# HDMI.net
KiCad netlist of a schematic drawn in Altium Designer
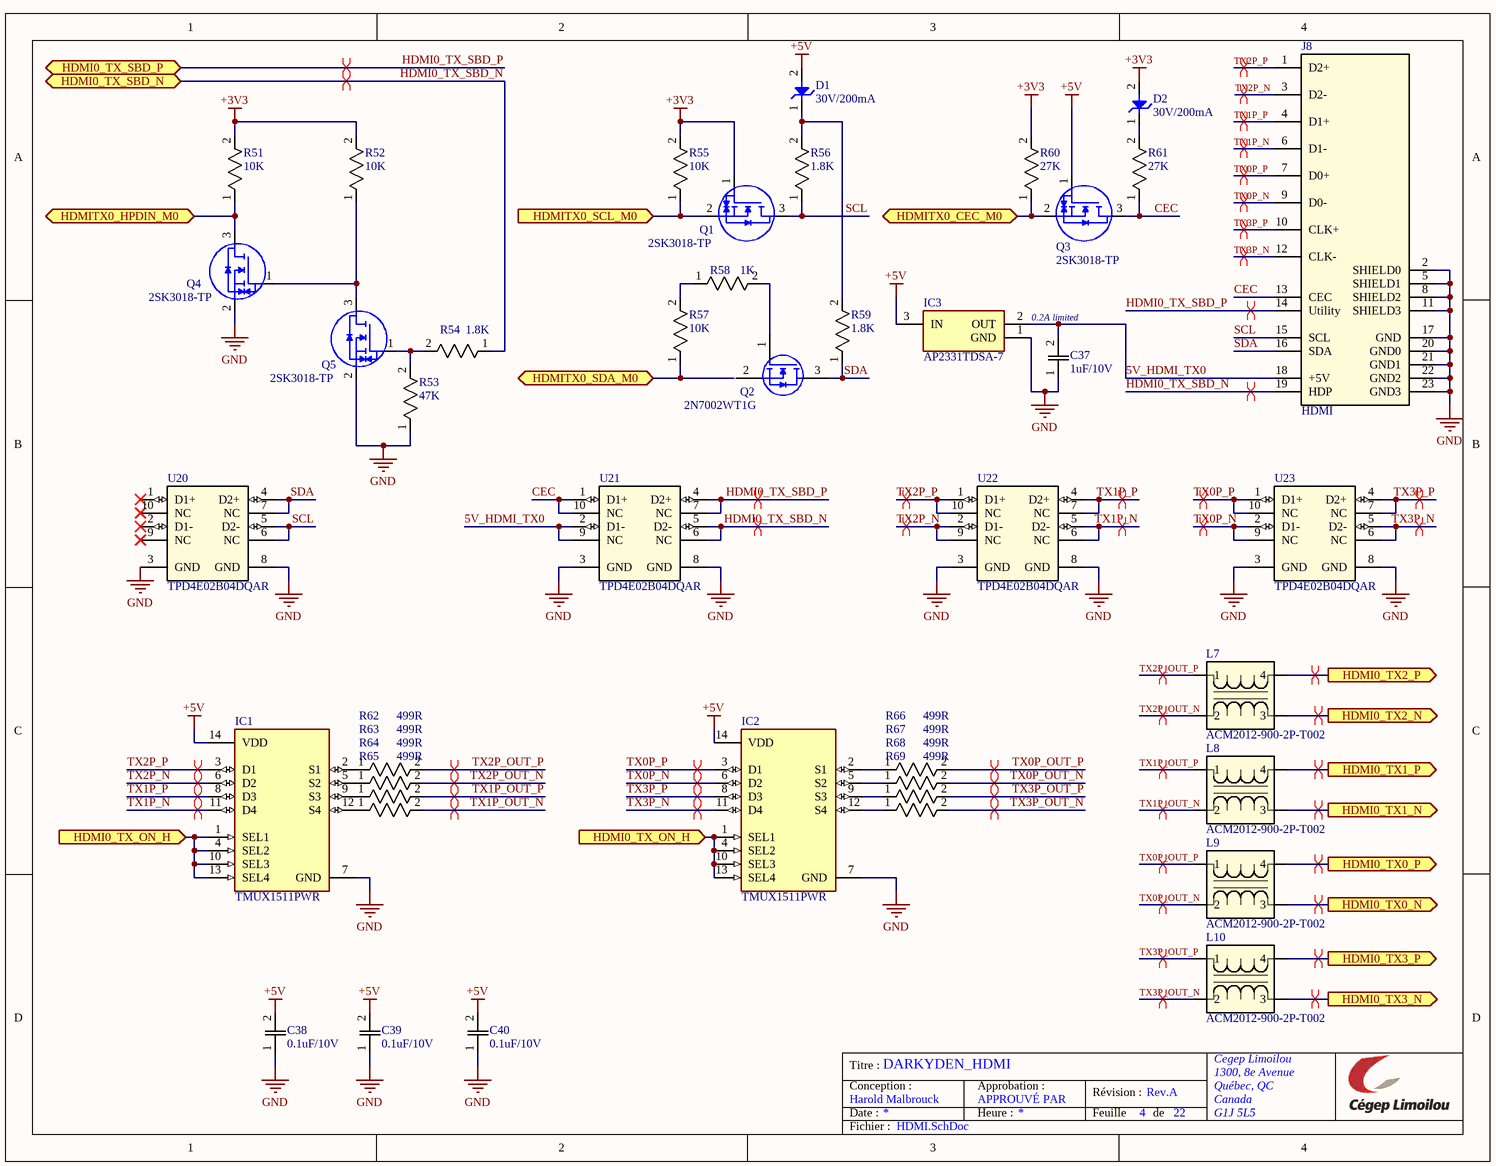
[diagram p0: HDMI.SchDoc]

(export (version "E")
  (design (tool "Eeschema 10.0.6"))
  (components
    (comp (ref "C37")
      (value "1uF/10V")
      (footprint "CAPC220145_88N_KEM")
      (description "Multilayer Ceramic Capacitors MLCC - SMD/SMT 10V 1uF X7R 0805 10%")
      (fields
        (field (name "MANUFACTURER") "KEMET")
        (field (name "MANUFACTURER PART NUMBER") "C0805C105K8RACTU")
      )
      (libsource (lib "C0805C105K8RACTU") (part "C0805C105K8RACTU"))
    )
    (comp (ref "C38")
      (value "0.1uF/10V")
      (footprint "CAPC220145_88N_KEM")
      (description "Cap Ceramic 0.1uF 10V X7R 5% Pad SMD 0805 125C T/R")
      (fields
        (field (name "MANUFACTURER") "KEMET")
        (field (name "MANUFACTURER PART NUMBER") "C0805C104J8RACTU")
      )
      (libsource (lib "C0805C104J8RACTU") (part "C0805C104J8RACTU"))
    )
    (comp (ref "C39")
      (value "0.1uF/10V")
      (footprint "CAPC220145_88N_KEM")
      (description "Cap Ceramic 0.1uF 10V X7R 5% Pad SMD 0805 125C T/R")
      (fields
        (field (name "MANUFACTURER") "KEMET")
        (field (name "MANUFACTURER PART NUMBER") "C0805C104J8RACTU")
      )
      (libsource (lib "C0805C104J8RACTU") (part "C0805C104J8RACTU"))
    )
    (comp (ref "C40")
      (value "0.1uF/10V")
      (footprint "CAPC220145_88N_KEM")
      (description "Cap Ceramic 0.1uF 10V X7R 5% Pad SMD 0805 125C T/R")
      (fields
        (field (name "MANUFACTURER") "KEMET")
        (field (name "MANUFACTURER PART NUMBER") "C0805C104J8RACTU")
      )
      (libsource (lib "C0805C104J8RACTU") (part "C0805C104J8RACTU"))
    )
    (comp (ref "D1")
      (value "30V/200mA")
      (footprint "SamacSys:SODFL1608X70N")
      (description "SCHOTTKY BARRIER DIODE Rectifier Diode, Schottky, 1 Phase, 1 Element, 0.2A, 30V V(RRM), Silicon")
      (fields
        (field (name "MANUFACTURER_PART_NUMBER") "RB521S30T1G")
        (field (name "MOUSER PART NUMBER") "863-RB521S30T1G")
      )
      (libsource (lib "SamacSys") (part "RB521S30T1G"))
    )
    (comp (ref "D2")
      (value "30V/200mA")
      (footprint "SamacSys:SODFL1608X70N")
      (description "SCHOTTKY BARRIER DIODE Rectifier Diode, Schottky, 1 Phase, 1 Element, 0.2A, 30V V(RRM), Silicon")
      (fields
        (field (name "MANUFACTURER_PART_NUMBER") "RB521S30T1G")
        (field (name "MOUSER PART NUMBER") "863-RB521S30T1G")
      )
      (libsource (lib "SamacSys") (part "RB521S30T1G"))
    )
    (comp (ref "IC1")
      (value "TMUX1511PWR")
      (footprint "SamacSys:SOP65P640X120-14N")
      (fields
        (field (name "MOUSER PART NUMBER") "595-TMUX1511PWR")
        (field (name "MANUFACTURER") "Texas Instruments")
      )
      (libsource (lib "SamacSys") (part "TMUX1511PWR"))
    )
    (comp (ref "IC2")
      (value "TMUX1511PWR")
      (footprint "SamacSys:SOP65P640X120-14N")
      (fields
        (field (name "MOUSER PART NUMBER") "595-TMUX1511PWR")
        (field (name "MANUFACTURER") "Texas Instruments")
      )
      (libsource (lib "SamacSys") (part "TMUX1511PWR"))
    )
    (comp (ref "IC3")
      (value "AP2331TDSA-7")
      (footprint "SamacSys:SOT96P240X110-3N")
      (description "USB Power Switch Single 5.2V 0.4A 3-Pin SOT-23 T/R")
      (fields (field (name "MOUSER PART NUMBER") "621-AP2331TDSA-7") (field (name "MANUFACTURER") "Diodes"))
      (libsource (lib "SamacSys") (part "AP2331TDSA-7"))
    )
    (comp (ref "J8")
      (value "HDMI")
      (footprint "CONN19_2001-1-2-21-00-BK_CNC")
      (description "2001-1-2-21-00-BK")
      (libsource (lib "HDMI") (part "HDMI"))
    )
    (comp (ref "L7")
      (value "ACM2012-900-2P-T002")
      (footprint "SamacSys:ACM20129002PT002")
      (description "Ferrite Beads Wirewound Common Mode Filter 90Ohm 100MHz 400mA 0805 T/R")
      (fields (field (name "MOUSER PART NUMBER") "810-ACM20129002PT002") (field (name "MANUFACTURER") "TDK"))
      (libsource (lib "SamacSys") (part "ACM2012-900-2P-T002"))
    )
    (comp (ref "L8")
      (value "ACM2012-900-2P-T002")
      (footprint "SamacSys:ACM20129002PT002")
      (description "Ferrite Beads Wirewound Common Mode Filter 90Ohm 100MHz 400mA 0805 T/R")
      (fields (field (name "MOUSER PART NUMBER") "810-ACM20129002PT002") (field (name "MANUFACTURER") "TDK"))
      (libsource (lib "SamacSys") (part "ACM2012-900-2P-T002"))
    )
    (comp (ref "L9")
      (value "ACM2012-900-2P-T002")
      (footprint "SamacSys:ACM20129002PT002")
      (description "Ferrite Beads Wirewound Common Mode Filter 90Ohm 100MHz 400mA 0805 T/R")
      (fields (field (name "MOUSER PART NUMBER") "810-ACM20129002PT002") (field (name "MANUFACTURER") "TDK"))
      (libsource (lib "SamacSys") (part "ACM2012-900-2P-T002"))
    )
    (comp (ref "L10")
      (value "ACM2012-900-2P-T002")
      (footprint "SamacSys:ACM20129002PT002")
      (description "Ferrite Beads Wirewound Common Mode Filter 90Ohm 100MHz 400mA 0805 T/R")
      (fields (field (name "MOUSER PART NUMBER") "810-ACM20129002PT002") (field (name "MANUFACTURER") "TDK"))
      (libsource (lib "SamacSys") (part "ACM2012-900-2P-T002"))
    )
    (comp (ref "Q1")
      (value "2SK3018-TP")
      (footprint "SamacSys:SOT65P228X120-3N")
      (description "N-Channel 30 V 100mA (Ta) 200mW (Ta) Surface Mount SOT-323")
      (fields (field (name "MOUSER PART NUMBER") "833-2SK3018-TP"))
      (libsource (lib "SamacSys") (part "2SK3018-TP"))
    )
    (comp (ref "Q2")
      (value "2N7002WT1G")
      (footprint "SOT-323-3_2P2X1P35_ONS")
      (description "No Description Available")
      (libsource (lib "2N7002WT1G") (part "2N7002WT1G"))
    )
    (comp (ref "Q3")
      (value "2SK3018-TP")
      (footprint "SamacSys:SOT65P228X120-3N")
      (description "N-Channel 30 V 100mA (Ta) 200mW (Ta) Surface Mount SOT-323")
      (fields (field (name "MOUSER PART NUMBER") "833-2SK3018-TP"))
      (libsource (lib "SamacSys") (part "2SK3018-TP"))
    )
    (comp (ref "Q4")
      (value "2SK3018-TP")
      (footprint "SamacSys:SOT65P228X120-3N")
      (description "N-Channel 30 V 100mA (Ta) 200mW (Ta) Surface Mount SOT-323")
      (fields (field (name "MOUSER PART NUMBER") "833-2SK3018-TP"))
      (libsource (lib "SamacSys") (part "2SK3018-TP"))
    )
    (comp (ref "Q5")
      (value "2SK3018-TP")
      (footprint "SamacSys:SOT65P228X120-3N")
      (description "N-Channel 30 V 100mA (Ta) 200mW (Ta) Surface Mount SOT-323")
      (fields (field (name "MOUSER PART NUMBER") "833-2SK3018-TP"))
      (libsource (lib "SamacSys") (part "2SK3018-TP"))
    )
    (comp (ref "R51")
      (value "10K")
      (footprint "SamacSys:ERJ3EKF1000V")
      (description "10K Ohm 5% Res Thick Film 0603  0.1W(1/10W) ±200ppm/C Pad SMD Automotive T/R")
      (fields
        (field (name "MANUFACTURER_PART_NUMBER") "ERJ-3GEYJ103V")
        (field (name "MOUSER PART NUMBER") "667-ERJ-3GEYJ103V")
      )
      (libsource (lib "SamacSys") (part "ERJ-3GEYJ103V"))
    )
    (comp (ref "R52")
      (value "10K")
      (footprint "SamacSys:ERJ3EKF1000V")
      (description "10K Ohm 5% Res Thick Film 0603  0.1W(1/10W) ±200ppm/C Pad SMD Automotive T/R")
      (fields
        (field (name "MANUFACTURER_PART_NUMBER") "ERJ-3GEYJ103V")
        (field (name "MOUSER PART NUMBER") "667-ERJ-3GEYJ103V")
      )
      (libsource (lib "SamacSys") (part "ERJ-3GEYJ103V"))
    )
    (comp (ref "R53")
      (value "47K")
      (footprint "RC0603N_PAN")
      (description "Resistor Thick Film 0603 47K Ohm 5% 1/10W 200ppm/C Molded SMD Punched Carrier T/R")
      (fields
        (field (name "MANUFACTURER") "Panasonic")
        (field (name "MANUFACTURER PART NUMBER") "ERJ-3GEYJ473V")
      )
      (libsource (lib "ERJ-3GEYJ473V") (part "ERJ-3GEYJ473V"))
    )
    (comp (ref "R54")
      (value "1.8K")
      (footprint "RC0603N_PAN")
      (description "SMD Chip Resistor, 1.8 kOhm, ± 5%, 100 mW, 0603 [1608 Metric], Thick Film, General Purpose")
      (fields
        (field (name "MANUFACTURER") "Panasonic")
        (field (name "MANUFACTURER PART NUMBER") "ERJ-3GEYJ182V")
      )
      (libsource (lib "ERJ-3GEYJ182V") (part "ERJ-3GEYJ182V"))
    )
    (comp (ref "R55")
      (value "10K")
      (footprint "SamacSys:ERJ3EKF1000V")
      (description "10K Ohm 5% Res Thick Film 0603  0.1W(1/10W) ±200ppm/C Pad SMD Automotive T/R")
      (fields
        (field (name "MANUFACTURER_PART_NUMBER") "ERJ-3GEYJ103V")
        (field (name "MOUSER PART NUMBER") "667-ERJ-3GEYJ103V")
      )
      (libsource (lib "SamacSys") (part "ERJ-3GEYJ103V"))
    )
    (comp (ref "R56")
      (value "1.8K")
      (footprint "RC0603N_PAN")
      (description "SMD Chip Resistor, 1.8 kOhm, ± 5%, 100 mW, 0603 [1608 Metric], Thick Film, General Purpose")
      (fields
        (field (name "MANUFACTURER") "Panasonic")
        (field (name "MANUFACTURER PART NUMBER") "ERJ-3GEYJ182V")
      )
      (libsource (lib "ERJ-3GEYJ182V") (part "ERJ-3GEYJ182V"))
    )
    (comp (ref "R57")
      (value "10K")
      (footprint "SamacSys:ERJ3EKF1000V")
      (description "10K Ohm 5% Res Thick Film 0603  0.1W(1/10W) ±200ppm/C Pad SMD Automotive T/R")
      (fields
        (field (name "MANUFACTURER_PART_NUMBER") "ERJ-3GEYJ103V")
        (field (name "MOUSER PART NUMBER") "667-ERJ-3GEYJ103V")
      )
      (libsource (lib "SamacSys") (part "ERJ-3GEYJ103V"))
    )
    (comp (ref "R58")
      (value "1K")
      (footprint "SamacSys:RESC1608X55N")
      (description "1K Ohm 1% 1/10W Res Thick Film 0603 ±100ppm/°C Molded SMD Punched Carrier T/R")
      (fields
        (field (name "MANUFACTURER_PART_NUMBER") "ERJ-3EKF1001V")
        (field (name "MOUSER PART NUMBER") "667-ERJ-3EKF1001V")
      )
      (libsource (lib "SamacSys") (part "ERJ-3EKF1001V"))
    )
    (comp (ref "R59")
      (value "1.8K")
      (footprint "RC0603N_PAN")
      (description "SMD Chip Resistor, 1.8 kOhm, ± 5%, 100 mW, 0603 [1608 Metric], Thick Film, General Purpose")
      (fields
        (field (name "MANUFACTURER") "Panasonic")
        (field (name "MANUFACTURER PART NUMBER") "ERJ-3GEYJ182V")
      )
      (libsource (lib "ERJ-3GEYJ182V") (part "ERJ-3GEYJ182V"))
    )
    (comp (ref "R60")
      (value "27K")
      (footprint "RC0603N_PAN")
      (description "Res Thick Film 0603 27K Ohm 1% 1/10W ±100ppm/°C Molded SMD Punched Carrier T/R")
      (fields
        (field (name "MANUFACTURER") "Panasonic")
        (field (name "MANUFACTURER PART NUMBER") "ERJ-3EKF2702V")
      )
      (libsource (lib "ERJ-3EKF2702V") (part "ERJ-3EKF2702V"))
    )
    (comp (ref "R61")
      (value "27K")
      (footprint "RC0603N_PAN")
      (description "Res Thick Film 0603 27K Ohm 1% 1/10W ±100ppm/°C Molded SMD Punched Carrier T/R")
      (fields
        (field (name "MANUFACTURER") "Panasonic")
        (field (name "MANUFACTURER PART NUMBER") "ERJ-3EKF2702V")
      )
      (libsource (lib "ERJ-3EKF2702V") (part "ERJ-3EKF2702V"))
    )
    (comp (ref "R62")
      (value "499R")
      (footprint "RC0603N_PAN")
      (description "SMD Chip Resistor, 499 Ohm, ï¿½ 1%, 100 mW, 0603 [1608 Metric], Thick Film, Precision")
      (fields
        (field (name "MANUFACTURER") "Panasonic")
        (field (name "MANUFACTURER PART NUMBER") "ERJ-3EKF4990V")
      )
      (libsource (lib "ERJ-3EKF4990V") (part "ERJ-3EKF4990V"))
    )
    (comp (ref "R63")
      (value "499R")
      (footprint "RC0603N_PAN")
      (description "SMD Chip Resistor, 499 Ohm, ï¿½ 1%, 100 mW, 0603 [1608 Metric], Thick Film, Precision")
      (fields
        (field (name "MANUFACTURER") "Panasonic")
        (field (name "MANUFACTURER PART NUMBER") "ERJ-3EKF4990V")
      )
      (libsource (lib "ERJ-3EKF4990V") (part "ERJ-3EKF4990V"))
    )
    (comp (ref "R64")
      (value "499R")
      (footprint "RC0603N_PAN")
      (description "SMD Chip Resistor, 499 Ohm, ï¿½ 1%, 100 mW, 0603 [1608 Metric], Thick Film, Precision")
      (fields
        (field (name "MANUFACTURER") "Panasonic")
        (field (name "MANUFACTURER PART NUMBER") "ERJ-3EKF4990V")
      )
      (libsource (lib "ERJ-3EKF4990V") (part "ERJ-3EKF4990V"))
    )
    (comp (ref "R65")
      (value "499R")
      (footprint "RC0603N_PAN")
      (description "SMD Chip Resistor, 499 Ohm, ï¿½ 1%, 100 mW, 0603 [1608 Metric], Thick Film, Precision")
      (fields
        (field (name "MANUFACTURER") "Panasonic")
        (field (name "MANUFACTURER PART NUMBER") "ERJ-3EKF4990V")
      )
      (libsource (lib "ERJ-3EKF4990V") (part "ERJ-3EKF4990V"))
    )
    (comp (ref "R66")
      (value "499R")
      (footprint "RC0603N_PAN")
      (description "SMD Chip Resistor, 499 Ohm, ï¿½ 1%, 100 mW, 0603 [1608 Metric], Thick Film, Precision")
      (fields
        (field (name "MANUFACTURER") "Panasonic")
        (field (name "MANUFACTURER PART NUMBER") "ERJ-3EKF4990V")
      )
      (libsource (lib "ERJ-3EKF4990V") (part "ERJ-3EKF4990V"))
    )
    (comp (ref "R67")
      (value "499R")
      (footprint "RC0603N_PAN")
      (description "SMD Chip Resistor, 499 Ohm, ï¿½ 1%, 100 mW, 0603 [1608 Metric], Thick Film, Precision")
      (fields
        (field (name "MANUFACTURER") "Panasonic")
        (field (name "MANUFACTURER PART NUMBER") "ERJ-3EKF4990V")
      )
      (libsource (lib "ERJ-3EKF4990V") (part "ERJ-3EKF4990V"))
    )
    (comp (ref "R68")
      (value "499R")
      (footprint "RC0603N_PAN")
      (description "SMD Chip Resistor, 499 Ohm, ï¿½ 1%, 100 mW, 0603 [1608 Metric], Thick Film, Precision")
      (fields
        (field (name "MANUFACTURER") "Panasonic")
        (field (name "MANUFACTURER PART NUMBER") "ERJ-3EKF4990V")
      )
      (libsource (lib "ERJ-3EKF4990V") (part "ERJ-3EKF4990V"))
    )
    (comp (ref "R69")
      (value "499R")
      (footprint "RC0603N_PAN")
      (description "SMD Chip Resistor, 499 Ohm, ï¿½ 1%, 100 mW, 0603 [1608 Metric], Thick Film, Precision")
      (fields
        (field (name "MANUFACTURER") "Panasonic")
        (field (name "MANUFACTURER PART NUMBER") "ERJ-3EKF4990V")
      )
      (libsource (lib "ERJ-3EKF4990V") (part "ERJ-3EKF4990V"))
    )
    (comp (ref "U20")
      (value "TPD4E02B04DQAR")
      (footprint "DQA0010A")
      (description "TVS DIODE 3.6V 8.8V 10USON / 4-Channel ESD Protection Diode for USB Type-C and HDMI 2.0")
      (fields (field (name "MANUFACTURER") "Texas Instruments"))
      (libsource (lib "TPD4E02B04DQAR") (part "TPD4E02B04DQAR"))
    )
    (comp (ref "U21")
      (value "TPD4E02B04DQAR")
      (footprint "DQA0010A")
      (description "TVS DIODE 3.6V 8.8V 10USON / 4-Channel ESD Protection Diode for USB Type-C and HDMI 2.0")
      (fields (field (name "MANUFACTURER") "Texas Instruments"))
      (libsource (lib "TPD4E02B04DQAR") (part "TPD4E02B04DQAR"))
    )
    (comp (ref "U22")
      (value "TPD4E02B04DQAR")
      (footprint "DQA0010A")
      (description "TVS DIODE 3.6V 8.8V 10USON / 4-Channel ESD Protection Diode for USB Type-C and HDMI 2.0")
      (fields (field (name "MANUFACTURER") "Texas Instruments"))
      (libsource (lib "TPD4E02B04DQAR") (part "TPD4E02B04DQAR"))
    )
    (comp (ref "U23")
      (value "TPD4E02B04DQAR")
      (footprint "DQA0010A")
      (description "TVS DIODE 3.6V 8.8V 10USON / 4-Channel ESD Protection Diode for USB Type-C and HDMI 2.0")
      (fields (field (name "MANUFACTURER") "Texas Instruments"))
      (libsource (lib "TPD4E02B04DQAR") (part "TPD4E02B04DQAR"))
    )
  )
  (nets
    (net (code "1") (name "+3V3") (class "Default")
      (node (ref "D2") (pin "2") (pinfunction "A_2") (pintype "passive"))
      (node (ref "Q1") (pin "1") (pinfunction "G_1") (pintype "passive"))
      (node (ref "R51") (pin "2") (pinfunction "2_2") (pintype "passive"))
      (node (ref "R52") (pin "2") (pinfunction "2_2") (pintype "passive"))
      (node (ref "R55") (pin "2") (pinfunction "2_2") (pintype "passive"))
      (node (ref "R60") (pin "2") (pinfunction "2_2") (pintype "passive"))
    )
    (net (code "2") (name "+5V") (class "Default")
      (node (ref "C38") (pin "2") (pinfunction "2_2") (pintype "passive"))
      (node (ref "C39") (pin "2") (pinfunction "2_2") (pintype "passive"))
      (node (ref "C40") (pin "2") (pinfunction "2_2") (pintype "passive"))
      (node (ref "D1") (pin "2") (pinfunction "A_2") (pintype "passive"))
      (node (ref "IC1") (pin "14") (pinfunction "VDD_14") (pintype "power_in"))
      (node (ref "IC2") (pin "14") (pinfunction "VDD_14") (pintype "power_in"))
      (node (ref "IC3") (pin "3") (pinfunction "IN_3") (pintype "passive"))
      (node (ref "Q3") (pin "1") (pinfunction "G_1") (pintype "passive"))
    )
    (net (code "3") (name "/5V_HDMI_TX0") (class "Default")
      (node (ref "C37") (pin "2") (pinfunction "2_2") (pintype "passive"))
      (node (ref "IC3") (pin "2") (pinfunction "OUT_2") (pintype "passive"))
      (node (ref "J8") (pin "18") (pinfunction "+5V_18") (pintype "passive"))
      (node (ref "U21") (pin "2") (pinfunction "D1-_2") (pintype "bidirectional"))
      (node (ref "U21") (pin "9") (pinfunction "NC_9") (pintype "passive"))
    )
    (net (code "4") (name "/CEC") (class "Default")
      (node (ref "J8") (pin "13") (pinfunction "CEC_13") (pintype "passive"))
      (node (ref "Q3") (pin "3") (pinfunction "D_3") (pintype "passive"))
      (node (ref "R61") (pin "1") (pinfunction "1_1") (pintype "passive"))
      (node (ref "U21") (pin "1") (pinfunction "D1+_1") (pintype "bidirectional"))
      (node (ref "U21") (pin "10") (pinfunction "NC_10") (pintype "passive"))
    )
    (net (code "5") (name "/HDMI0_TX0_N") (class "Default")
      (node (ref "L9") (pin "3") (pinfunction "3_3") (pintype "passive"))
    )
    (net (code "6") (name "/HDMI0_TX0_P") (class "Default")
      (node (ref "L9") (pin "4") (pinfunction "4_4") (pintype "passive"))
    )
    (net (code "7") (name "/HDMI0_TX1_N") (class "Default")
      (node (ref "L8") (pin "3") (pinfunction "3_3") (pintype "passive"))
    )
    (net (code "8") (name "/HDMI0_TX1_P") (class "Default")
      (node (ref "L8") (pin "4") (pinfunction "4_4") (pintype "passive"))
    )
    (net (code "9") (name "/HDMI0_TX2_N") (class "Default")
      (node (ref "L7") (pin "3") (pinfunction "3_3") (pintype "passive"))
    )
    (net (code "10") (name "/HDMI0_TX2_P") (class "Default")
      (node (ref "L7") (pin "4") (pinfunction "4_4") (pintype "passive"))
    )
    (net (code "11") (name "/HDMI0_TX3_N") (class "Default")
      (node (ref "L10") (pin "3") (pinfunction "3_3") (pintype "passive"))
    )
    (net (code "12") (name "/HDMI0_TX3_P") (class "Default")
      (node (ref "L10") (pin "4") (pinfunction "4_4") (pintype "passive"))
    )
    (net (code "13") (name "/HDMI0_TX_ON_H") (class "Default")
      (node (ref "IC1") (pin "1") (pinfunction "SEL1_1") (pintype "input"))
      (node (ref "IC1") (pin "10") (pinfunction "SEL3_10") (pintype "input"))
      (node (ref "IC1") (pin "13") (pinfunction "SEL4_13") (pintype "input"))
      (node (ref "IC1") (pin "4") (pinfunction "SEL2_4") (pintype "input"))
      (node (ref "IC2") (pin "1") (pinfunction "SEL1_1") (pintype "input"))
      (node (ref "IC2") (pin "10") (pinfunction "SEL3_10") (pintype "input"))
      (node (ref "IC2") (pin "13") (pinfunction "SEL4_13") (pintype "input"))
      (node (ref "IC2") (pin "4") (pinfunction "SEL2_4") (pintype "input"))
    )
    (net (code "14") (name "/HDMI0_TX_SBD_N") (class "Default")
      (node (ref "J8") (pin "19") (pinfunction "HDP_19") (pintype "passive"))
      (node (ref "R54") (pin "1") (pinfunction "1_1") (pintype "passive"))
      (node (ref "U21") (pin "5") (pinfunction "D2-_5") (pintype "bidirectional"))
      (node (ref "U21") (pin "6") (pinfunction "NC_6") (pintype "passive"))
    )
    (net (code "15") (name "/HDMI0_TX_SBD_P") (class "Default")
      (node (ref "J8") (pin "14") (pinfunction "Utility_14") (pintype "passive"))
      (node (ref "U21") (pin "4") (pinfunction "D2+_4") (pintype "bidirectional"))
      (node (ref "U21") (pin "7") (pinfunction "NC_7") (pintype "passive"))
    )
    (net (code "16") (name "/HDMITX0_CEC_M0") (class "Default")
      (node (ref "Q3") (pin "2") (pinfunction "S_2") (pintype "passive"))
      (node (ref "R60") (pin "1") (pinfunction "1_1") (pintype "passive"))
    )
    (net (code "17") (name "/HDMITX0_HPDIN_M0") (class "Default")
      (node (ref "Q4") (pin "3") (pinfunction "D_3") (pintype "passive"))
      (node (ref "R51") (pin "1") (pinfunction "1_1") (pintype "passive"))
    )
    (net (code "18") (name "/HDMITX0_SCL_M0") (class "Default")
      (node (ref "Q1") (pin "2") (pinfunction "S_2") (pintype "passive"))
      (node (ref "R55") (pin "1") (pinfunction "1_1") (pintype "passive"))
    )
    (net (code "19") (name "/HDMITX0_SDA_M0") (class "Default")
      (node (ref "R57") (pin "1") (pinfunction "1_1") (pintype "passive"))
    )
    (net (code "20") (name "/SCL") (class "Default")
      (node (ref "J8") (pin "15") (pinfunction "SCL_15") (pintype "passive"))
      (node (ref "Q1") (pin "3") (pinfunction "D_3") (pintype "passive"))
      (node (ref "R56") (pin "1") (pinfunction "1_1") (pintype "passive"))
      (node (ref "U20") (pin "5") (pinfunction "D2-_5") (pintype "bidirectional"))
      (node (ref "U20") (pin "6") (pinfunction "NC_6") (pintype "passive"))
    )
    (net (code "21") (name "/SDA") (class "Default")
      (node (ref "J8") (pin "16") (pinfunction "SDA_16") (pintype "passive"))
      (node (ref "Q2") (pin "3") (pinfunction "DRAIN_3") (pintype "passive"))
      (node (ref "R59") (pin "1") (pinfunction "1_1") (pintype "passive"))
      (node (ref "U20") (pin "4") (pinfunction "D2+_4") (pintype "bidirectional"))
      (node (ref "U20") (pin "7") (pinfunction "NC_7") (pintype "passive"))
    )
    (net (code "22") (name "/TX0P_N") (class "Default")
      (node (ref "IC2") (pin "6") (pinfunction "D2_6") (pintype "bidirectional"))
      (node (ref "J8") (pin "9") (pinfunction "D0-_9") (pintype "passive"))
      (node (ref "U23") (pin "2") (pinfunction "D1-_2") (pintype "bidirectional"))
      (node (ref "U23") (pin "9") (pinfunction "NC_9") (pintype "passive"))
    )
    (net (code "23") (name "/TX0P_OUT_N") (class "Default")
      (node (ref "L9") (pin "2") (pinfunction "2_2") (pintype "passive"))
      (node (ref "R67") (pin "2") (pinfunction "2_2") (pintype "passive"))
    )
    (net (code "24") (name "/TX0P_OUT_P") (class "Default")
      (node (ref "L9") (pin "1") (pinfunction "1_1") (pintype "passive"))
      (node (ref "R66") (pin "2") (pinfunction "2_2") (pintype "passive"))
    )
    (net (code "25") (name "/TX0P_P") (class "Default")
      (node (ref "IC2") (pin "3") (pinfunction "D1_3") (pintype "bidirectional"))
      (node (ref "J8") (pin "7") (pinfunction "D0+_7") (pintype "passive"))
      (node (ref "U23") (pin "1") (pinfunction "D1+_1") (pintype "bidirectional"))
      (node (ref "U23") (pin "10") (pinfunction "NC_10") (pintype "passive"))
    )
    (net (code "26") (name "/TX1P_N") (class "Default")
      (node (ref "IC1") (pin "11") (pinfunction "D4_11") (pintype "bidirectional"))
      (node (ref "J8") (pin "6") (pinfunction "D1-_6") (pintype "passive"))
      (node (ref "U22") (pin "5") (pinfunction "D2-_5") (pintype "bidirectional"))
      (node (ref "U22") (pin "6") (pinfunction "NC_6") (pintype "passive"))
    )
    (net (code "27") (name "/TX1P_OUT_N") (class "Default")
      (node (ref "L8") (pin "2") (pinfunction "2_2") (pintype "passive"))
      (node (ref "R65") (pin "2") (pinfunction "2_2") (pintype "passive"))
    )
    (net (code "28") (name "/TX1P_OUT_P") (class "Default")
      (node (ref "L8") (pin "1") (pinfunction "1_1") (pintype "passive"))
      (node (ref "R64") (pin "2") (pinfunction "2_2") (pintype "passive"))
    )
    (net (code "29") (name "/TX1P_P") (class "Default")
      (node (ref "IC1") (pin "8") (pinfunction "D3_8") (pintype "bidirectional"))
      (node (ref "J8") (pin "4") (pinfunction "D1+_4") (pintype "passive"))
      (node (ref "U22") (pin "4") (pinfunction "D2+_4") (pintype "bidirectional"))
      (node (ref "U22") (pin "7") (pinfunction "NC_7") (pintype "passive"))
    )
    (net (code "30") (name "/TX2P_N") (class "Default")
      (node (ref "IC1") (pin "6") (pinfunction "D2_6") (pintype "bidirectional"))
      (node (ref "J8") (pin "3") (pinfunction "D2-_3") (pintype "passive"))
      (node (ref "U22") (pin "2") (pinfunction "D1-_2") (pintype "bidirectional"))
      (node (ref "U22") (pin "9") (pinfunction "NC_9") (pintype "passive"))
    )
    (net (code "31") (name "/TX2P_OUT_N") (class "Default")
      (node (ref "L7") (pin "2") (pinfunction "2_2") (pintype "passive"))
      (node (ref "R63") (pin "2") (pinfunction "2_2") (pintype "passive"))
    )
    (net (code "32") (name "/TX2P_OUT_P") (class "Default")
      (node (ref "L7") (pin "1") (pinfunction "1_1") (pintype "passive"))
      (node (ref "R62") (pin "2") (pinfunction "2_2") (pintype "passive"))
    )
    (net (code "33") (name "/TX2P_P") (class "Default")
      (node (ref "IC1") (pin "3") (pinfunction "D1_3") (pintype "bidirectional"))
      (node (ref "J8") (pin "1") (pinfunction "D2+_1") (pintype "passive"))
      (node (ref "U22") (pin "1") (pinfunction "D1+_1") (pintype "bidirectional"))
      (node (ref "U22") (pin "10") (pinfunction "NC_10") (pintype "passive"))
    )
    (net (code "34") (name "/TX3P_N") (class "Default")
      (node (ref "IC2") (pin "11") (pinfunction "D4_11") (pintype "bidirectional"))
      (node (ref "J8") (pin "12") (pinfunction "CLK-_12") (pintype "passive"))
      (node (ref "U23") (pin "5") (pinfunction "D2-_5") (pintype "bidirectional"))
      (node (ref "U23") (pin "6") (pinfunction "NC_6") (pintype "passive"))
    )
    (net (code "35") (name "/TX3P_OUT_N") (class "Default")
      (node (ref "L10") (pin "2") (pinfunction "2_2") (pintype "passive"))
      (node (ref "R69") (pin "2") (pinfunction "2_2") (pintype "passive"))
    )
    (net (code "36") (name "/TX3P_OUT_P") (class "Default")
      (node (ref "L10") (pin "1") (pinfunction "1_1") (pintype "passive"))
      (node (ref "R68") (pin "2") (pinfunction "2_2") (pintype "passive"))
    )
    (net (code "37") (name "/TX3P_P") (class "Default")
      (node (ref "IC2") (pin "8") (pinfunction "D3_8") (pintype "bidirectional"))
      (node (ref "J8") (pin "10") (pinfunction "CLK+_10") (pintype "passive"))
      (node (ref "U23") (pin "4") (pinfunction "D2+_4") (pintype "bidirectional"))
      (node (ref "U23") (pin "7") (pinfunction "NC_7") (pintype "passive"))
    )
    (net (code "38") (name "GND") (class "Default")
      (node (ref "C37") (pin "1") (pinfunction "1_1") (pintype "passive"))
      (node (ref "C38") (pin "1") (pinfunction "1_1") (pintype "passive"))
      (node (ref "C39") (pin "1") (pinfunction "1_1") (pintype "passive"))
      (node (ref "C40") (pin "1") (pinfunction "1_1") (pintype "passive"))
      (node (ref "IC1") (pin "7") (pinfunction "GND_7") (pintype "power_in"))
      (node (ref "IC2") (pin "7") (pinfunction "GND_7") (pintype "power_in"))
      (node (ref "IC3") (pin "1") (pinfunction "GND_1") (pintype "passive"))
      (node (ref "J8") (pin "11") (pinfunction "SHIELD3_11") (pintype "passive"))
      (node (ref "J8") (pin "17") (pinfunction "GND_17") (pintype "passive"))
      (node (ref "J8") (pin "2") (pinfunction "SHIELD0_2") (pintype "passive"))
      (node (ref "J8") (pin "20") (pinfunction "GND0_20") (pintype "passive"))
      (node (ref "J8") (pin "21") (pinfunction "GND1_21") (pintype "passive"))
      (node (ref "J8") (pin "22") (pinfunction "GND2_22") (pintype "passive"))
      (node (ref "J8") (pin "23") (pinfunction "GND3_23") (pintype "passive"))
      (node (ref "J8") (pin "5") (pinfunction "SHIELD1_5") (pintype "passive"))
      (node (ref "J8") (pin "8") (pinfunction "SHIELD2_8") (pintype "passive"))
      (node (ref "Q4") (pin "2") (pinfunction "S_2") (pintype "passive"))
      (node (ref "Q5") (pin "2") (pinfunction "S_2") (pintype "passive"))
      (node (ref "R53") (pin "1") (pinfunction "1_1") (pintype "passive"))
      (node (ref "U20") (pin "3") (pinfunction "GND_3") (pintype "passive"))
      (node (ref "U20") (pin "8") (pinfunction "GND_8") (pintype "passive"))
      (node (ref "U21") (pin "3") (pinfunction "GND_3") (pintype "passive"))
      (node (ref "U21") (pin "8") (pinfunction "GND_8") (pintype "passive"))
      (node (ref "U22") (pin "3") (pinfunction "GND_3") (pintype "passive"))
      (node (ref "U22") (pin "8") (pinfunction "GND_8") (pintype "passive"))
      (node (ref "U23") (pin "3") (pinfunction "GND_3") (pintype "passive"))
      (node (ref "U23") (pin "8") (pinfunction "GND_8") (pintype "passive"))
    )
    (net (code "39") (name "Net-(D1-K)") (class "Default")
      (node (ref "D1") (pin "1") (pinfunction "K_1") (pintype "passive"))
      (node (ref "R56") (pin "2") (pinfunction "2_2") (pintype "passive"))
      (node (ref "R59") (pin "2") (pinfunction "2_2") (pintype "passive"))
    )
    (net (code "40") (name "Net-(D2-K)") (class "Default")
      (node (ref "D2") (pin "1") (pinfunction "K_1") (pintype "passive"))
      (node (ref "R61") (pin "2") (pinfunction "2_2") (pintype "passive"))
    )
    (net (code "41") (name "Net-(IC1-S1)") (class "Default")
      (node (ref "IC1") (pin "2") (pinfunction "S1_2") (pintype "bidirectional"))
      (node (ref "R62") (pin "1") (pinfunction "1_1") (pintype "passive"))
    )
    (net (code "42") (name "Net-(IC1-S2)") (class "Default")
      (node (ref "IC1") (pin "5") (pinfunction "S2_5") (pintype "bidirectional"))
      (node (ref "R63") (pin "1") (pinfunction "1_1") (pintype "passive"))
    )
    (net (code "43") (name "Net-(IC1-S3)") (class "Default")
      (node (ref "IC1") (pin "9") (pinfunction "S3_9") (pintype "bidirectional"))
      (node (ref "R64") (pin "1") (pinfunction "1_1") (pintype "passive"))
    )
    (net (code "44") (name "Net-(IC1-S4)") (class "Default")
      (node (ref "IC1") (pin "12") (pinfunction "S4_12") (pintype "bidirectional"))
      (node (ref "R65") (pin "1") (pinfunction "1_1") (pintype "passive"))
    )
    (net (code "45") (name "Net-(IC2-S1)") (class "Default")
      (node (ref "IC2") (pin "2") (pinfunction "S1_2") (pintype "bidirectional"))
      (node (ref "R66") (pin "1") (pinfunction "1_1") (pintype "passive"))
    )
    (net (code "46") (name "Net-(IC2-S2)") (class "Default")
      (node (ref "IC2") (pin "5") (pinfunction "S2_5") (pintype "bidirectional"))
      (node (ref "R67") (pin "1") (pinfunction "1_1") (pintype "passive"))
    )
    (net (code "47") (name "Net-(IC2-S3)") (class "Default")
      (node (ref "IC2") (pin "9") (pinfunction "S3_9") (pintype "bidirectional"))
      (node (ref "R68") (pin "1") (pinfunction "1_1") (pintype "passive"))
    )
    (net (code "48") (name "Net-(IC2-S4)") (class "Default")
      (node (ref "IC2") (pin "12") (pinfunction "S4_12") (pintype "bidirectional"))
      (node (ref "R69") (pin "1") (pinfunction "1_1") (pintype "passive"))
    )
    (net (code "49") (name "Net-(Q2-GATE)") (class "Default")
      (node (ref "Q2") (pin "1") (pinfunction "GATE_1") (pintype "passive"))
      (node (ref "R58") (pin "2") (pinfunction "2_2") (pintype "passive"))
    )
    (net (code "50") (name "Net-(Q4-G)") (class "Default")
      (node (ref "Q4") (pin "1") (pinfunction "G_1") (pintype "passive"))
      (node (ref "Q5") (pin "3") (pinfunction "D_3") (pintype "passive"))
      (node (ref "R52") (pin "1") (pinfunction "1_1") (pintype "passive"))
    )
    (net (code "51") (name "Net-(Q5-G)") (class "Default")
      (node (ref "Q5") (pin "1") (pinfunction "G_1") (pintype "passive"))
      (node (ref "R53") (pin "2") (pinfunction "2_2") (pintype "passive"))
      (node (ref "R54") (pin "2") (pinfunction "2_2") (pintype "passive"))
    )
    (net (code "52") (name "Net-(R57-Pad2)") (class "Default")
      (node (ref "R57") (pin "2") (pinfunction "2_2") (pintype "passive"))
      (node (ref "R58") (pin "1") (pinfunction "1_1") (pintype "passive"))
    )
    (net (code "53") (name "unconnected-(Q2-SOURCE-Pad2)") (class "Default")
      (node (ref "Q2") (pin "2") (pinfunction "SOURCE_2") (pintype "passive"))
    )
    (net (code "54") (name "unconnected-(U20-D1+-Pad1)") (class "Default")
      (node (ref "U20") (pin "1") (pinfunction "D1+_1") (pintype "bidirectional+no_connect"))
    )
    (net (code "55") (name "unconnected-(U20-D1--Pad2)") (class "Default")
      (node (ref "U20") (pin "2") (pinfunction "D1-_2") (pintype "bidirectional+no_connect"))
    )
    (net (code "56") (name "unconnected-(U20-NC-Pad9)") (class "Default")
      (node (ref "U20") (pin "9") (pinfunction "NC_9") (pintype "passive+no_connect"))
    )
    (net (code "57") (name "unconnected-(U20-NC-Pad10)") (class "Default")
      (node (ref "U20") (pin "10") (pinfunction "NC_10") (pintype "passive+no_connect"))
    )
  )
)
